# LEDBoard.net
KiCad netlist of a schematic drawn in EAGLE
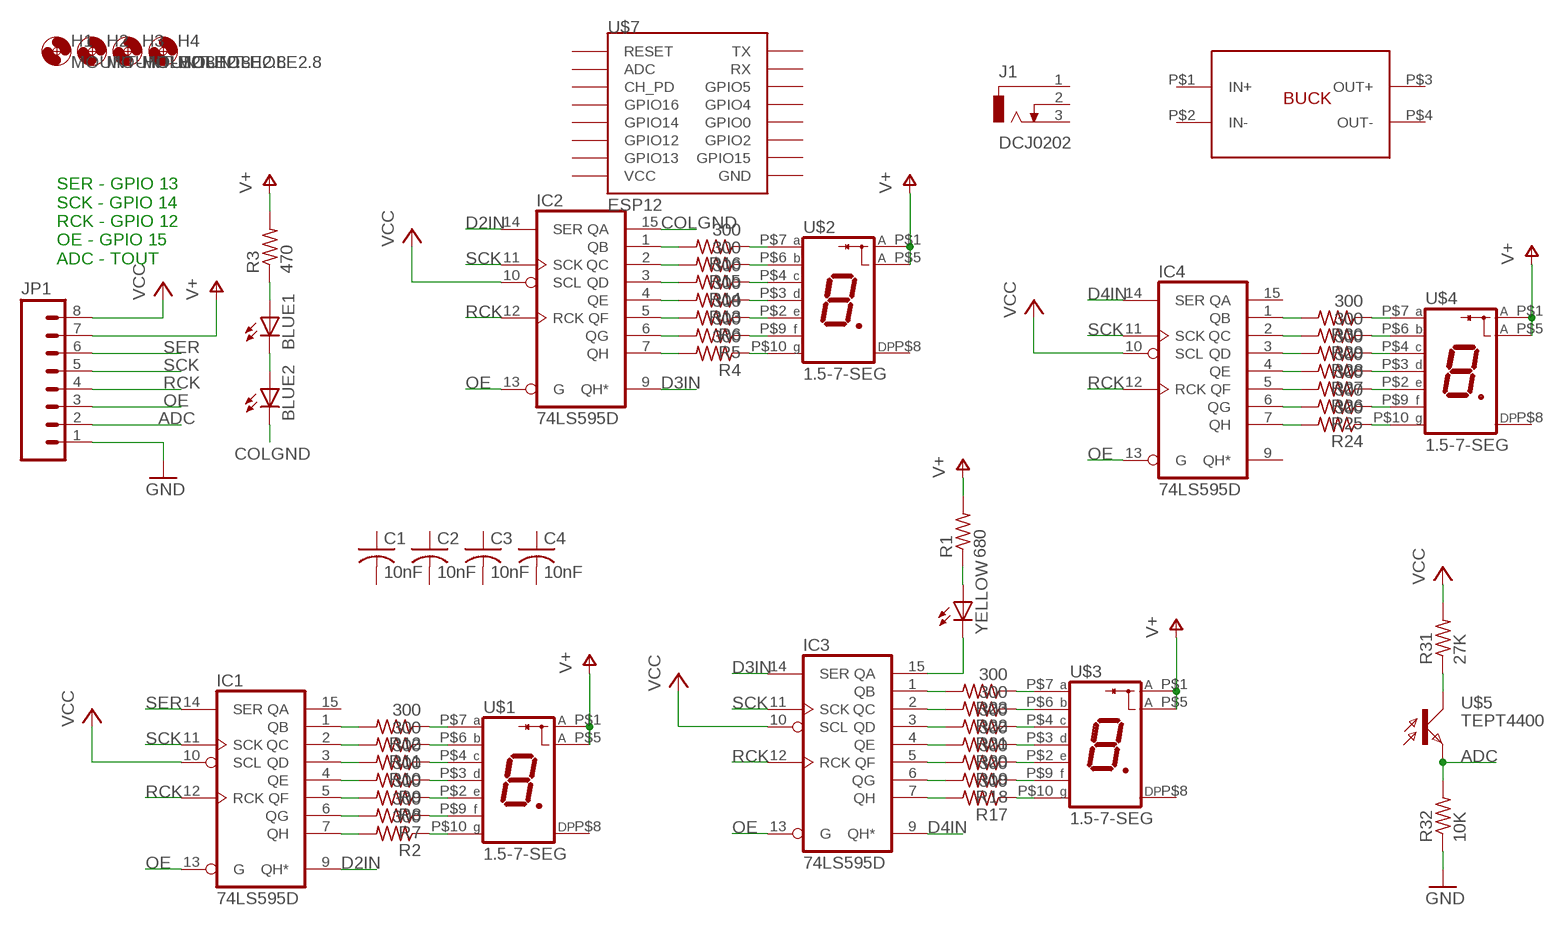
[diagram p0: schematic, sheet 1]

(export (version "E")
  (design (tool "Eeschema 10.0.6"))
  (components
    (comp (ref "BLUE1")
      (value "LED3MM")
      (footprint "eagle-import:LED3MM")
      (libsource (lib "eagle-import") (part "LED3MM"))
    )
    (comp (ref "BLUE2")
      (value "LED3MM")
      (footprint "eagle-import:LED3MM")
      (libsource (lib "eagle-import") (part "LED3MM"))
    )
    (comp (ref "C1")
      (value "10nF")
      (footprint "eagle-import:C0805K")
      (libsource (lib "eagle-import") (part "C-USC0805K"))
    )
    (comp (ref "C2")
      (value "10nF")
      (footprint "eagle-import:C0805K")
      (libsource (lib "eagle-import") (part "C-USC0805K"))
    )
    (comp (ref "C3")
      (value "10nF")
      (footprint "eagle-import:C0805K")
      (libsource (lib "eagle-import") (part "C-USC0805K"))
    )
    (comp (ref "C4")
      (value "10nF")
      (footprint "eagle-import:C0805K")
      (libsource (lib "eagle-import") (part "C-USC0805K"))
    )
    (comp (ref "H1")
      (value "MOUNT-HOLE2.8")
      (footprint "eagle-import:2,8")
      (libsource (lib "eagle-import") (part "MOUNT-HOLE2.8"))
    )
    (comp (ref "H2")
      (value "MOUNT-HOLE2.8")
      (footprint "eagle-import:2,8")
      (libsource (lib "eagle-import") (part "MOUNT-HOLE2.8"))
    )
    (comp (ref "H3")
      (value "MOUNT-HOLE2.8")
      (footprint "eagle-import:2,8")
      (libsource (lib "eagle-import") (part "MOUNT-HOLE2.8"))
    )
    (comp (ref "H4")
      (value "MOUNT-HOLE2.8")
      (footprint "eagle-import:2,8")
      (libsource (lib "eagle-import") (part "MOUNT-HOLE2.8"))
    )
    (comp (ref "IC1")
      (value "74LS595D")
      (footprint "eagle-import:SO16")
      (libsource (lib "eagle-import") (part "74595DLS"))
    )
    (comp (ref "IC2")
      (value "74LS595D")
      (footprint "eagle-import:SO16")
      (libsource (lib "eagle-import") (part "74595DLS"))
    )
    (comp (ref "IC3")
      (value "74LS595D")
      (footprint "eagle-import:SO16")
      (libsource (lib "eagle-import") (part "74595DLS"))
    )
    (comp (ref "IC4")
      (value "74LS595D")
      (footprint "eagle-import:SO16")
      (libsource (lib "eagle-import") (part "74595DLS"))
    )
    (comp (ref "J1")
      (value "DCJ0202")
      (footprint "eagle-import:DCJ0202")
      (libsource (lib "eagle-import") (part "DCJ0202"))
    )
    (comp (ref "JP1")
      (value "M08SMD-MALE")
      (footprint "eagle-import:1X08_SMD_MALE")
      (libsource (lib "eagle-import") (part "M08SMD-MALE"))
    )
    (comp (ref "R1")
      (value "680")
      (footprint "eagle-import:M0805")
      (libsource (lib "eagle-import") (part "R-US_M0805"))
    )
    (comp (ref "R2")
      (value "300")
      (footprint "eagle-import:M0805")
      (libsource (lib "eagle-import") (part "R-US_M0805"))
    )
    (comp (ref "R3")
      (value "470")
      (footprint "eagle-import:M0805")
      (libsource (lib "eagle-import") (part "R-US_M0805"))
    )
    (comp (ref "R4")
      (value "300")
      (footprint "eagle-import:M0805")
      (libsource (lib "eagle-import") (part "R-US_M0805"))
    )
    (comp (ref "R5")
      (value "300")
      (footprint "eagle-import:M0805")
      (libsource (lib "eagle-import") (part "R-US_M0805"))
    )
    (comp (ref "R6")
      (value "300")
      (footprint "eagle-import:M0805")
      (libsource (lib "eagle-import") (part "R-US_M0805"))
    )
    (comp (ref "R7")
      (value "300")
      (footprint "eagle-import:M0805")
      (libsource (lib "eagle-import") (part "R-US_M0805"))
    )
    (comp (ref "R8")
      (value "300")
      (footprint "eagle-import:M0805")
      (libsource (lib "eagle-import") (part "R-US_M0805"))
    )
    (comp (ref "R9")
      (value "300")
      (footprint "eagle-import:M0805")
      (libsource (lib "eagle-import") (part "R-US_M0805"))
    )
    (comp (ref "R10")
      (value "300")
      (footprint "eagle-import:M0805")
      (libsource (lib "eagle-import") (part "R-US_M0805"))
    )
    (comp (ref "R11")
      (value "300")
      (footprint "eagle-import:M0805")
      (libsource (lib "eagle-import") (part "R-US_M0805"))
    )
    (comp (ref "R12")
      (value "300")
      (footprint "eagle-import:M0805")
      (libsource (lib "eagle-import") (part "R-US_M0805"))
    )
    (comp (ref "R13")
      (value "300")
      (footprint "eagle-import:M0805")
      (libsource (lib "eagle-import") (part "R-US_M0805"))
    )
    (comp (ref "R14")
      (value "300")
      (footprint "eagle-import:M0805")
      (libsource (lib "eagle-import") (part "R-US_M0805"))
    )
    (comp (ref "R15")
      (value "300")
      (footprint "eagle-import:M0805")
      (libsource (lib "eagle-import") (part "R-US_M0805"))
    )
    (comp (ref "R16")
      (value "300")
      (footprint "eagle-import:M0805")
      (libsource (lib "eagle-import") (part "R-US_M0805"))
    )
    (comp (ref "R17")
      (value "300")
      (footprint "eagle-import:M0805")
      (libsource (lib "eagle-import") (part "R-US_M0805"))
    )
    (comp (ref "R18")
      (value "300")
      (footprint "eagle-import:M0805")
      (libsource (lib "eagle-import") (part "R-US_M0805"))
    )
    (comp (ref "R19")
      (value "300")
      (footprint "eagle-import:M0805")
      (libsource (lib "eagle-import") (part "R-US_M0805"))
    )
    (comp (ref "R20")
      (value "300")
      (footprint "eagle-import:M0805")
      (libsource (lib "eagle-import") (part "R-US_M0805"))
    )
    (comp (ref "R21")
      (value "300")
      (footprint "eagle-import:M0805")
      (libsource (lib "eagle-import") (part "R-US_M0805"))
    )
    (comp (ref "R22")
      (value "300")
      (footprint "eagle-import:M0805")
      (libsource (lib "eagle-import") (part "R-US_M0805"))
    )
    (comp (ref "R23")
      (value "300")
      (footprint "eagle-import:M0805")
      (libsource (lib "eagle-import") (part "R-US_M0805"))
    )
    (comp (ref "R24")
      (value "300")
      (footprint "eagle-import:M0805")
      (libsource (lib "eagle-import") (part "R-US_M0805"))
    )
    (comp (ref "R25")
      (value "300")
      (footprint "eagle-import:M0805")
      (libsource (lib "eagle-import") (part "R-US_M0805"))
    )
    (comp (ref "R26")
      (value "300")
      (footprint "eagle-import:M0805")
      (libsource (lib "eagle-import") (part "R-US_M0805"))
    )
    (comp (ref "R27")
      (value "300")
      (footprint "eagle-import:M0805")
      (libsource (lib "eagle-import") (part "R-US_M0805"))
    )
    (comp (ref "R28")
      (value "300")
      (footprint "eagle-import:M0805")
      (libsource (lib "eagle-import") (part "R-US_M0805"))
    )
    (comp (ref "R29")
      (value "300")
      (footprint "eagle-import:M0805")
      (libsource (lib "eagle-import") (part "R-US_M0805"))
    )
    (comp (ref "R30")
      (value "300")
      (footprint "eagle-import:M0805")
      (libsource (lib "eagle-import") (part "R-US_M0805"))
    )
    (comp (ref "R31")
      (value "27K")
      (footprint "eagle-import:M0805")
      (libsource (lib "eagle-import") (part "R-US_M0805"))
    )
    (comp (ref "R32")
      (value "10K")
      (footprint "eagle-import:M0805")
      (libsource (lib "eagle-import") (part "R-US_M0805"))
    )
    (comp (ref "U$1")
      (value "1.5-7-SEG")
      (footprint "eagle-import:1.5-7-SEG")
      (libsource (lib "eagle-import") (part "1.5-7-SEG"))
    )
    (comp (ref "U$2")
      (value "1.5-7-SEG")
      (footprint "eagle-import:1.5-7-SEG")
      (libsource (lib "eagle-import") (part "1.5-7-SEG"))
    )
    (comp (ref "U$3")
      (value "1.5-7-SEG")
      (footprint "eagle-import:1.5-7-SEG")
      (libsource (lib "eagle-import") (part "1.5-7-SEG"))
    )
    (comp (ref "U$4")
      (value "1.5-7-SEG")
      (footprint "eagle-import:1.5-7-SEG")
      (libsource (lib "eagle-import") (part "1.5-7-SEG"))
    )
    (comp (ref "U$5")
      (value "TEPT4400")
      (footprint "eagle-import:T1")
      (libsource (lib "eagle-import") (part "TEPT4400"))
    )
    (comp (ref "U$6")
      (value "BUCK_CONV")
      (footprint "eagle-import:BUCK_CONV")
      (libsource (lib "eagle-import") (part "BUCK_CONV"))
    )
    (comp (ref "U$7")
      (value "ESP12")
      (footprint "eagle-import:ESP12")
      (libsource (lib "eagle-import") (part "ESP12"))
    )
    (comp (ref "YELLOW")
      (value "LED3MM")
      (footprint "eagle-import:LED3MM")
      (libsource (lib "eagle-import") (part "LED3MM"))
    )
  )
  (nets
    (net (code "1") (name "/ADC") (class "Default")
      (node (ref "JP1") (pin "2") (pinfunction "2_2") (pintype "passive"))
      (node (ref "R32") (pin "2") (pinfunction "2_2") (pintype "passive"))
      (node (ref "U$5") (pin "A") (pinfunction "E_A") (pintype "passive"))
    )
    (net (code "2") (name "/COLGND") (class "Default")
      (node (ref "BLUE2") (pin "K") (pinfunction "C_K") (pintype "passive"))
      (node (ref "IC2") (pin "15") (pinfunction "QA_15") (pintype "tri_state"))
    )
    (net (code "3") (name "/D2IN") (class "Default")
      (node (ref "IC1") (pin "9") (pinfunction "QH*_9") (pintype "tri_state"))
      (node (ref "IC2") (pin "14") (pinfunction "SER_14") (pintype "input"))
    )
    (net (code "4") (name "/D3IN") (class "Default")
      (node (ref "IC2") (pin "9") (pinfunction "QH*_9") (pintype "tri_state"))
      (node (ref "IC3") (pin "14") (pinfunction "SER_14") (pintype "input"))
    )
    (net (code "5") (name "/D4IN") (class "Default")
      (node (ref "IC3") (pin "9") (pinfunction "QH*_9") (pintype "tri_state"))
      (node (ref "IC4") (pin "14") (pinfunction "SER_14") (pintype "input"))
    )
    (net (code "6") (name "/OE") (class "Default")
      (node (ref "IC1") (pin "13") (pinfunction "G_13") (pintype "input"))
      (node (ref "IC2") (pin "13") (pinfunction "G_13") (pintype "input"))
      (node (ref "IC3") (pin "13") (pinfunction "G_13") (pintype "input"))
      (node (ref "IC4") (pin "13") (pinfunction "G_13") (pintype "input"))
      (node (ref "JP1") (pin "3") (pinfunction "3_3") (pintype "passive"))
    )
    (net (code "7") (name "/RCK") (class "Default")
      (node (ref "IC1") (pin "12") (pinfunction "RCK_12") (pintype "input"))
      (node (ref "IC2") (pin "12") (pinfunction "RCK_12") (pintype "input"))
      (node (ref "IC3") (pin "12") (pinfunction "RCK_12") (pintype "input"))
      (node (ref "IC4") (pin "12") (pinfunction "RCK_12") (pintype "input"))
      (node (ref "JP1") (pin "4") (pinfunction "4_4") (pintype "passive"))
    )
    (net (code "8") (name "/SCK") (class "Default")
      (node (ref "IC1") (pin "11") (pinfunction "SCK_11") (pintype "input"))
      (node (ref "IC2") (pin "11") (pinfunction "SCK_11") (pintype "input"))
      (node (ref "IC3") (pin "11") (pinfunction "SCK_11") (pintype "input"))
      (node (ref "IC4") (pin "11") (pinfunction "SCK_11") (pintype "input"))
      (node (ref "JP1") (pin "5") (pinfunction "5_5") (pintype "passive"))
    )
    (net (code "9") (name "/SER") (class "Default")
      (node (ref "IC1") (pin "14") (pinfunction "SER_14") (pintype "input"))
      (node (ref "JP1") (pin "6") (pinfunction "6_6") (pintype "passive"))
    )
    (net (code "10") (name "GND") (class "Default")
      (node (ref "JP1") (pin "1") (pinfunction "1_1") (pintype "passive"))
      (node (ref "R32") (pin "1") (pinfunction "1_1") (pintype "passive"))
    )
    (net (code "11") (name "Net-(BLUE1-C)") (class "Default")
      (node (ref "BLUE1") (pin "K") (pinfunction "C_K") (pintype "passive"))
      (node (ref "BLUE2") (pin "A") (pinfunction "A_A") (pintype "passive"))
    )
    (net (code "12") (name "Net-(BLUE1-PadA)") (class "Default")
      (node (ref "BLUE1") (pin "A") (pinfunction "A_A") (pintype "passive"))
      (node (ref "R3") (pin "1") (pinfunction "1_1") (pintype "passive"))
    )
    (net (code "13") (name "Net-(IC1A-QB)") (class "Default")
      (node (ref "IC1") (pin "1") (pinfunction "QB_1") (pintype "tri_state"))
      (node (ref "R12") (pin "2") (pinfunction "2_2") (pintype "passive"))
    )
    (net (code "14") (name "Net-(IC1A-QC)") (class "Default")
      (node (ref "IC1") (pin "2") (pinfunction "QC_2") (pintype "tri_state"))
      (node (ref "R11") (pin "2") (pinfunction "2_2") (pintype "passive"))
    )
    (net (code "15") (name "Net-(IC1A-QD)") (class "Default")
      (node (ref "IC1") (pin "3") (pinfunction "QD_3") (pintype "tri_state"))
      (node (ref "R10") (pin "2") (pinfunction "2_2") (pintype "passive"))
    )
    (net (code "16") (name "Net-(IC1A-QE)") (class "Default")
      (node (ref "IC1") (pin "4") (pinfunction "QE_4") (pintype "tri_state"))
      (node (ref "R9") (pin "2") (pinfunction "2_2") (pintype "passive"))
    )
    (net (code "17") (name "Net-(IC1A-QF)") (class "Default")
      (node (ref "IC1") (pin "5") (pinfunction "QF_5") (pintype "tri_state"))
      (node (ref "R8") (pin "2") (pinfunction "2_2") (pintype "passive"))
    )
    (net (code "18") (name "Net-(IC1A-QG)") (class "Default")
      (node (ref "IC1") (pin "6") (pinfunction "QG_6") (pintype "tri_state"))
      (node (ref "R7") (pin "2") (pinfunction "2_2") (pintype "passive"))
    )
    (net (code "19") (name "Net-(IC1A-QH)") (class "Default")
      (node (ref "IC1") (pin "7") (pinfunction "QH_7") (pintype "tri_state"))
      (node (ref "R2") (pin "2") (pinfunction "2_2") (pintype "passive"))
    )
    (net (code "20") (name "Net-(IC2A-QB)") (class "Default")
      (node (ref "IC2") (pin "1") (pinfunction "QB_1") (pintype "tri_state"))
      (node (ref "R16") (pin "2") (pinfunction "2_2") (pintype "passive"))
    )
    (net (code "21") (name "Net-(IC2A-QC)") (class "Default")
      (node (ref "IC2") (pin "2") (pinfunction "QC_2") (pintype "tri_state"))
      (node (ref "R15") (pin "2") (pinfunction "2_2") (pintype "passive"))
    )
    (net (code "22") (name "Net-(IC2A-QD)") (class "Default")
      (node (ref "IC2") (pin "3") (pinfunction "QD_3") (pintype "tri_state"))
      (node (ref "R14") (pin "2") (pinfunction "2_2") (pintype "passive"))
    )
    (net (code "23") (name "Net-(IC2A-QE)") (class "Default")
      (node (ref "IC2") (pin "4") (pinfunction "QE_4") (pintype "tri_state"))
      (node (ref "R13") (pin "2") (pinfunction "2_2") (pintype "passive"))
    )
    (net (code "24") (name "Net-(IC2A-QF)") (class "Default")
      (node (ref "IC2") (pin "5") (pinfunction "QF_5") (pintype "tri_state"))
      (node (ref "R6") (pin "2") (pinfunction "2_2") (pintype "passive"))
    )
    (net (code "25") (name "Net-(IC2A-QG)") (class "Default")
      (node (ref "IC2") (pin "6") (pinfunction "QG_6") (pintype "tri_state"))
      (node (ref "R5") (pin "2") (pinfunction "2_2") (pintype "passive"))
    )
    (net (code "26") (name "Net-(IC2A-QH)") (class "Default")
      (node (ref "IC2") (pin "7") (pinfunction "QH_7") (pintype "tri_state"))
      (node (ref "R4") (pin "2") (pinfunction "2_2") (pintype "passive"))
    )
    (net (code "27") (name "Net-(IC3A-QA)") (class "Default")
      (node (ref "IC3") (pin "15") (pinfunction "QA_15") (pintype "tri_state"))
      (node (ref "YELLOW") (pin "K") (pinfunction "C_K") (pintype "passive"))
    )
    (net (code "28") (name "Net-(IC3A-QB)") (class "Default")
      (node (ref "IC3") (pin "1") (pinfunction "QB_1") (pintype "tri_state"))
      (node (ref "R23") (pin "2") (pinfunction "2_2") (pintype "passive"))
    )
    (net (code "29") (name "Net-(IC3A-QC)") (class "Default")
      (node (ref "IC3") (pin "2") (pinfunction "QC_2") (pintype "tri_state"))
      (node (ref "R22") (pin "2") (pinfunction "2_2") (pintype "passive"))
    )
    (net (code "30") (name "Net-(IC3A-QD)") (class "Default")
      (node (ref "IC3") (pin "3") (pinfunction "QD_3") (pintype "tri_state"))
      (node (ref "R21") (pin "2") (pinfunction "2_2") (pintype "passive"))
    )
    (net (code "31") (name "Net-(IC3A-QE)") (class "Default")
      (node (ref "IC3") (pin "4") (pinfunction "QE_4") (pintype "tri_state"))
      (node (ref "R20") (pin "2") (pinfunction "2_2") (pintype "passive"))
    )
    (net (code "32") (name "Net-(IC3A-QF)") (class "Default")
      (node (ref "IC3") (pin "5") (pinfunction "QF_5") (pintype "tri_state"))
      (node (ref "R19") (pin "2") (pinfunction "2_2") (pintype "passive"))
    )
    (net (code "33") (name "Net-(IC3A-QG)") (class "Default")
      (node (ref "IC3") (pin "6") (pinfunction "QG_6") (pintype "tri_state"))
      (node (ref "R18") (pin "2") (pinfunction "2_2") (pintype "passive"))
    )
    (net (code "34") (name "Net-(IC3A-QH)") (class "Default")
      (node (ref "IC3") (pin "7") (pinfunction "QH_7") (pintype "tri_state"))
      (node (ref "R17") (pin "2") (pinfunction "2_2") (pintype "passive"))
    )
    (net (code "35") (name "Net-(IC4A-QB)") (class "Default")
      (node (ref "IC4") (pin "1") (pinfunction "QB_1") (pintype "tri_state"))
      (node (ref "R30") (pin "2") (pinfunction "2_2") (pintype "passive"))
    )
    (net (code "36") (name "Net-(IC4A-QC)") (class "Default")
      (node (ref "IC4") (pin "2") (pinfunction "QC_2") (pintype "tri_state"))
      (node (ref "R29") (pin "2") (pinfunction "2_2") (pintype "passive"))
    )
    (net (code "37") (name "Net-(IC4A-QD)") (class "Default")
      (node (ref "IC4") (pin "3") (pinfunction "QD_3") (pintype "tri_state"))
      (node (ref "R28") (pin "2") (pinfunction "2_2") (pintype "passive"))
    )
    (net (code "38") (name "Net-(IC4A-QE)") (class "Default")
      (node (ref "IC4") (pin "4") (pinfunction "QE_4") (pintype "tri_state"))
      (node (ref "R27") (pin "2") (pinfunction "2_2") (pintype "passive"))
    )
    (net (code "39") (name "Net-(IC4A-QF)") (class "Default")
      (node (ref "IC4") (pin "5") (pinfunction "QF_5") (pintype "tri_state"))
      (node (ref "R26") (pin "2") (pinfunction "2_2") (pintype "passive"))
    )
    (net (code "40") (name "Net-(IC4A-QG)") (class "Default")
      (node (ref "IC4") (pin "6") (pinfunction "QG_6") (pintype "tri_state"))
      (node (ref "R25") (pin "2") (pinfunction "2_2") (pintype "passive"))
    )
    (net (code "41") (name "Net-(IC4A-QH)") (class "Default")
      (node (ref "IC4") (pin "7") (pinfunction "QH_7") (pintype "tri_state"))
      (node (ref "R24") (pin "2") (pinfunction "2_2") (pintype "passive"))
    )
    (net (code "42") (name "Net-(R1-Pad1)") (class "Default")
      (node (ref "R1") (pin "1") (pinfunction "1_1") (pintype "passive"))
      (node (ref "YELLOW") (pin "A") (pinfunction "A_A") (pintype "passive"))
    )
    (net (code "43") (name "Net-(R12-Pad1)") (class "Default")
      (node (ref "R12") (pin "1") (pinfunction "1_1") (pintype "passive"))
      (node (ref "U$1") (pin "P$7") (pinfunction "A_P$7") (pintype "passive"))
    )
    (net (code "44") (name "Net-(R16-Pad1)") (class "Default")
      (node (ref "R16") (pin "1") (pinfunction "1_1") (pintype "passive"))
      (node (ref "U$2") (pin "P$7") (pinfunction "A_P$7") (pintype "passive"))
    )
    (net (code "45") (name "Net-(R23-Pad1)") (class "Default")
      (node (ref "R23") (pin "1") (pinfunction "1_1") (pintype "passive"))
      (node (ref "U$3") (pin "P$7") (pinfunction "A_P$7") (pintype "passive"))
    )
    (net (code "46") (name "Net-(R30-Pad1)") (class "Default")
      (node (ref "R30") (pin "1") (pinfunction "1_1") (pintype "passive"))
      (node (ref "U$4") (pin "P$7") (pinfunction "A_P$7") (pintype "passive"))
    )
    (net (code "47") (name "Net-(U$1-B)") (class "Default")
      (node (ref "R11") (pin "1") (pinfunction "1_1") (pintype "passive"))
      (node (ref "U$1") (pin "P$6") (pinfunction "B_P$6") (pintype "passive"))
    )
    (net (code "48") (name "Net-(U$1-C)") (class "Default")
      (node (ref "R10") (pin "1") (pinfunction "1_1") (pintype "passive"))
      (node (ref "U$1") (pin "P$4") (pinfunction "C_P$4") (pintype "passive"))
    )
    (net (code "49") (name "Net-(U$1-D)") (class "Default")
      (node (ref "R9") (pin "1") (pinfunction "1_1") (pintype "passive"))
      (node (ref "U$1") (pin "P$3") (pinfunction "D_P$3") (pintype "passive"))
    )
    (net (code "50") (name "Net-(U$1-E)") (class "Default")
      (node (ref "R8") (pin "1") (pinfunction "1_1") (pintype "passive"))
      (node (ref "U$1") (pin "P$2") (pinfunction "E_P$2") (pintype "passive"))
    )
    (net (code "51") (name "Net-(U$1-F)") (class "Default")
      (node (ref "R7") (pin "1") (pinfunction "1_1") (pintype "passive"))
      (node (ref "U$1") (pin "P$9") (pinfunction "F_P$9") (pintype "passive"))
    )
    (net (code "52") (name "Net-(U$1-G)") (class "Default")
      (node (ref "R2") (pin "1") (pinfunction "1_1") (pintype "passive"))
      (node (ref "U$1") (pin "P$10") (pinfunction "G_P$10") (pintype "passive"))
    )
    (net (code "53") (name "Net-(U$2-B)") (class "Default")
      (node (ref "R15") (pin "1") (pinfunction "1_1") (pintype "passive"))
      (node (ref "U$2") (pin "P$6") (pinfunction "B_P$6") (pintype "passive"))
    )
    (net (code "54") (name "Net-(U$2-C)") (class "Default")
      (node (ref "R14") (pin "1") (pinfunction "1_1") (pintype "passive"))
      (node (ref "U$2") (pin "P$4") (pinfunction "C_P$4") (pintype "passive"))
    )
    (net (code "55") (name "Net-(U$2-D)") (class "Default")
      (node (ref "R13") (pin "1") (pinfunction "1_1") (pintype "passive"))
      (node (ref "U$2") (pin "P$3") (pinfunction "D_P$3") (pintype "passive"))
    )
    (net (code "56") (name "Net-(U$2-E)") (class "Default")
      (node (ref "R6") (pin "1") (pinfunction "1_1") (pintype "passive"))
      (node (ref "U$2") (pin "P$2") (pinfunction "E_P$2") (pintype "passive"))
    )
    (net (code "57") (name "Net-(U$2-F)") (class "Default")
      (node (ref "R5") (pin "1") (pinfunction "1_1") (pintype "passive"))
      (node (ref "U$2") (pin "P$9") (pinfunction "F_P$9") (pintype "passive"))
    )
    (net (code "58") (name "Net-(U$2-G)") (class "Default")
      (node (ref "R4") (pin "1") (pinfunction "1_1") (pintype "passive"))
      (node (ref "U$2") (pin "P$10") (pinfunction "G_P$10") (pintype "passive"))
    )
    (net (code "59") (name "Net-(U$3-B)") (class "Default")
      (node (ref "R22") (pin "1") (pinfunction "1_1") (pintype "passive"))
      (node (ref "U$3") (pin "P$6") (pinfunction "B_P$6") (pintype "passive"))
    )
    (net (code "60") (name "Net-(U$3-C)") (class "Default")
      (node (ref "R21") (pin "1") (pinfunction "1_1") (pintype "passive"))
      (node (ref "U$3") (pin "P$4") (pinfunction "C_P$4") (pintype "passive"))
    )
    (net (code "61") (name "Net-(U$3-D)") (class "Default")
      (node (ref "R20") (pin "1") (pinfunction "1_1") (pintype "passive"))
      (node (ref "U$3") (pin "P$3") (pinfunction "D_P$3") (pintype "passive"))
    )
    (net (code "62") (name "Net-(U$3-E)") (class "Default")
      (node (ref "R19") (pin "1") (pinfunction "1_1") (pintype "passive"))
      (node (ref "U$3") (pin "P$2") (pinfunction "E_P$2") (pintype "passive"))
    )
    (net (code "63") (name "Net-(U$3-F)") (class "Default")
      (node (ref "R18") (pin "1") (pinfunction "1_1") (pintype "passive"))
      (node (ref "U$3") (pin "P$9") (pinfunction "F_P$9") (pintype "passive"))
    )
    (net (code "64") (name "Net-(U$3-G)") (class "Default")
      (node (ref "R17") (pin "1") (pinfunction "1_1") (pintype "passive"))
      (node (ref "U$3") (pin "P$10") (pinfunction "G_P$10") (pintype "passive"))
    )
    (net (code "65") (name "Net-(U$4-B)") (class "Default")
      (node (ref "R29") (pin "1") (pinfunction "1_1") (pintype "passive"))
      (node (ref "U$4") (pin "P$6") (pinfunction "B_P$6") (pintype "passive"))
    )
    (net (code "66") (name "Net-(U$4-C)") (class "Default")
      (node (ref "R28") (pin "1") (pinfunction "1_1") (pintype "passive"))
      (node (ref "U$4") (pin "P$4") (pinfunction "C_P$4") (pintype "passive"))
    )
    (net (code "67") (name "Net-(U$4-D)") (class "Default")
      (node (ref "R27") (pin "1") (pinfunction "1_1") (pintype "passive"))
      (node (ref "U$4") (pin "P$3") (pinfunction "D_P$3") (pintype "passive"))
    )
    (net (code "68") (name "Net-(U$4-E)") (class "Default")
      (node (ref "R26") (pin "1") (pinfunction "1_1") (pintype "passive"))
      (node (ref "U$4") (pin "P$2") (pinfunction "E_P$2") (pintype "passive"))
    )
    (net (code "69") (name "Net-(U$4-F)") (class "Default")
      (node (ref "R25") (pin "1") (pinfunction "1_1") (pintype "passive"))
      (node (ref "U$4") (pin "P$9") (pinfunction "F_P$9") (pintype "passive"))
    )
    (net (code "70") (name "Net-(U$4-G)") (class "Default")
      (node (ref "R24") (pin "1") (pinfunction "1_1") (pintype "passive"))
      (node (ref "U$4") (pin "P$10") (pinfunction "G_P$10") (pintype "passive"))
    )
    (net (code "71") (name "Net-(U$5-C)") (class "Default")
      (node (ref "R31") (pin "1") (pinfunction "1_1") (pintype "passive"))
      (node (ref "U$5") (pin "K") (pinfunction "C_K") (pintype "passive"))
    )
    (net (code "72") (name "V+") (class "Default")
      (node (ref "JP1") (pin "7") (pinfunction "7_7") (pintype "passive"))
      (node (ref "R1") (pin "2") (pinfunction "2_2") (pintype "passive"))
      (node (ref "R3") (pin "2") (pinfunction "2_2") (pintype "passive"))
      (node (ref "U$1") (pin "P$1") (pinfunction "A_P$1") (pintype "passive"))
      (node (ref "U$1") (pin "P$5") (pinfunction "A_P$5") (pintype "passive"))
      (node (ref "U$2") (pin "P$1") (pinfunction "A_P$1") (pintype "passive"))
      (node (ref "U$2") (pin "P$5") (pinfunction "A_P$5") (pintype "passive"))
      (node (ref "U$3") (pin "P$1") (pinfunction "A_P$1") (pintype "passive"))
      (node (ref "U$3") (pin "P$5") (pinfunction "A_P$5") (pintype "passive"))
      (node (ref "U$4") (pin "P$1") (pinfunction "A_P$1") (pintype "passive"))
      (node (ref "U$4") (pin "P$5") (pinfunction "A_P$5") (pintype "passive"))
    )
    (net (code "73") (name "VCC") (class "Default")
      (node (ref "IC1") (pin "10") (pinfunction "SCL_10") (pintype "input"))
      (node (ref "IC2") (pin "10") (pinfunction "SCL_10") (pintype "input"))
      (node (ref "IC3") (pin "10") (pinfunction "SCL_10") (pintype "input"))
      (node (ref "IC4") (pin "10") (pinfunction "SCL_10") (pintype "input"))
      (node (ref "JP1") (pin "8") (pinfunction "8_8") (pintype "passive"))
      (node (ref "R31") (pin "2") (pinfunction "2_2") (pintype "passive"))
    )
    (net (code "74") (name "unconnected-(C1-Pad1)") (class "Default")
      (node (ref "C1") (pin "1") (pinfunction "1_1") (pintype "passive"))
    )
    (net (code "75") (name "unconnected-(C1-Pad2)") (class "Default")
      (node (ref "C1") (pin "2") (pinfunction "2_2") (pintype "passive"))
    )
    (net (code "76") (name "unconnected-(C2-Pad1)") (class "Default")
      (node (ref "C2") (pin "1") (pinfunction "1_1") (pintype "passive"))
    )
    (net (code "77") (name "unconnected-(C2-Pad2)") (class "Default")
      (node (ref "C2") (pin "2") (pinfunction "2_2") (pintype "passive"))
    )
    (net (code "78") (name "unconnected-(C3-Pad1)") (class "Default")
      (node (ref "C3") (pin "1") (pinfunction "1_1") (pintype "passive"))
    )
    (net (code "79") (name "unconnected-(C3-Pad2)") (class "Default")
      (node (ref "C3") (pin "2") (pinfunction "2_2") (pintype "passive"))
    )
    (net (code "80") (name "unconnected-(C4-Pad1)") (class "Default")
      (node (ref "C4") (pin "1") (pinfunction "1_1") (pintype "passive"))
    )
    (net (code "81") (name "unconnected-(C4-Pad2)") (class "Default")
      (node (ref "C4") (pin "2") (pinfunction "2_2") (pintype "passive"))
    )
    (net (code "82") (name "unconnected-(IC1A-QA-Pad15)") (class "Default")
      (node (ref "IC1") (pin "15") (pinfunction "QA_15") (pintype "tri_state"))
    )
    (net (code "83") (name "unconnected-(IC4A-QA-Pad15)") (class "Default")
      (node (ref "IC4") (pin "15") (pinfunction "QA_15") (pintype "tri_state"))
    )
    (net (code "84") (name "unconnected-(IC4A-QH*-Pad9)") (class "Default")
      (node (ref "IC4") (pin "9") (pinfunction "QH*_9") (pintype "tri_state"))
    )
    (net (code "85") (name "unconnected-(J1-Pad1)") (class "Default")
      (node (ref "J1") (pin "1") (pinfunction "1_1") (pintype "passive"))
    )
    (net (code "86") (name "unconnected-(J1-Pad2)") (class "Default")
      (node (ref "J1") (pin "2") (pinfunction "2_2") (pintype "passive"))
    )
    (net (code "87") (name "unconnected-(J1-Pad3)") (class "Default")
      (node (ref "J1") (pin "3") (pinfunction "3_3") (pintype "passive"))
    )
    (net (code "88") (name "unconnected-(U$1-DP-PadP$8)") (class "Default")
      (node (ref "U$1") (pin "P$8") (pinfunction "DP_P$8") (pintype "passive"))
    )
    (net (code "89") (name "unconnected-(U$2-DP-PadP$8)") (class "Default")
      (node (ref "U$2") (pin "P$8") (pinfunction "DP_P$8") (pintype "passive"))
    )
    (net (code "90") (name "unconnected-(U$3-DP-PadP$8)") (class "Default")
      (node (ref "U$3") (pin "P$8") (pinfunction "DP_P$8") (pintype "passive"))
    )
    (net (code "91") (name "unconnected-(U$4-DP-PadP$8)") (class "Default")
      (node (ref "U$4") (pin "P$8") (pinfunction "DP_P$8") (pintype "passive"))
    )
    (net (code "92") (name "unconnected-(U$6-IN+-PadP$1)") (class "Default")
      (node (ref "U$6") (pin "P$1") (pinfunction "IN+_P$1") (pintype "bidirectional"))
    )
    (net (code "93") (name "unconnected-(U$6-IN--PadP$2)") (class "Default")
      (node (ref "U$6") (pin "P$2") (pinfunction "IN-_P$2") (pintype "bidirectional"))
    )
    (net (code "94") (name "unconnected-(U$6-OUT+-PadP$3)") (class "Default")
      (node (ref "U$6") (pin "P$3") (pinfunction "OUT+_P$3") (pintype "bidirectional"))
    )
    (net (code "95") (name "unconnected-(U$6-OUT--PadP$4)") (class "Default")
      (node (ref "U$6") (pin "P$4") (pinfunction "OUT-_P$4") (pintype "bidirectional"))
    )
    (net (code "96") (name "unconnected-(U$7-PadADC)") (class "Default")
      (node (ref "U$7") (pin "ADC") (pinfunction "ADC_ADC") (pintype "bidirectional"))
    )
    (net (code "97") (name "unconnected-(U$7-PadCH_PD)") (class "Default")
      (node (ref "U$7") (pin "CH_PD") (pinfunction "CH_PD_CH_PD") (pintype "bidirectional"))
    )
    (net (code "98") (name "unconnected-(U$7-PadGND)") (class "Default")
      (node (ref "U$7") (pin "GND") (pinfunction "GND_GND") (pintype "bidirectional"))
    )
    (net (code "99") (name "unconnected-(U$7-PadGPIO0)") (class "Default")
      (node (ref "U$7") (pin "GPIO0") (pinfunction "GPIO0_GPIO0") (pintype "bidirectional"))
    )
    (net (code "100") (name "unconnected-(U$7-PadGPIO2)") (class "Default")
      (node (ref "U$7") (pin "GPIO2") (pinfunction "GPIO2_GPIO2") (pintype "bidirectional"))
    )
    (net (code "101") (name "unconnected-(U$7-PadGPIO4)") (class "Default")
      (node (ref "U$7") (pin "GPIO4") (pinfunction "GPIO4_GPIO4") (pintype "bidirectional"))
    )
    (net (code "102") (name "unconnected-(U$7-PadGPIO5)") (class "Default")
      (node (ref "U$7") (pin "GPIO5") (pinfunction "GPIO5_GPIO5") (pintype "bidirectional"))
    )
    (net (code "103") (name "unconnected-(U$7-PadGPIO12)") (class "Default")
      (node (ref "U$7") (pin "GPIO12") (pinfunction "GPIO12_GPIO12") (pintype "bidirectional"))
    )
    (net (code "104") (name "unconnected-(U$7-PadGPIO13)") (class "Default")
      (node (ref "U$7") (pin "GPIO13") (pinfunction "GPIO13_GPIO13") (pintype "bidirectional"))
    )
    (net (code "105") (name "unconnected-(U$7-PadGPIO14)") (class "Default")
      (node (ref "U$7") (pin "GPIO14") (pinfunction "GPIO14_GPIO14") (pintype "bidirectional"))
    )
    (net (code "106") (name "unconnected-(U$7-PadGPIO15)") (class "Default")
      (node (ref "U$7") (pin "GPIO15") (pinfunction "GPIO15_GPIO15") (pintype "bidirectional"))
    )
    (net (code "107") (name "unconnected-(U$7-PadGPIO16)") (class "Default")
      (node (ref "U$7") (pin "GPIO16") (pinfunction "GPIO16_GPIO16") (pintype "bidirectional"))
    )
    (net (code "108") (name "unconnected-(U$7-PadRESET)") (class "Default")
      (node (ref "U$7") (pin "RESET") (pinfunction "RESET_RESET") (pintype "bidirectional"))
    )
    (net (code "109") (name "unconnected-(U$7-PadRX)") (class "Default")
      (node (ref "U$7") (pin "RX") (pinfunction "RX_RX") (pintype "bidirectional"))
    )
    (net (code "110") (name "unconnected-(U$7-PadTX)") (class "Default")
      (node (ref "U$7") (pin "TX") (pinfunction "TX_TX") (pintype "bidirectional"))
    )
    (net (code "111") (name "unconnected-(U$7-PadVCC)") (class "Default")
      (node (ref "U$7") (pin "VCC") (pinfunction "VCC_VCC") (pintype "bidirectional"))
    )
  )
)
